# EasyEDA_Source.net
KiCad netlist of a schematic drawn in EasyEDA
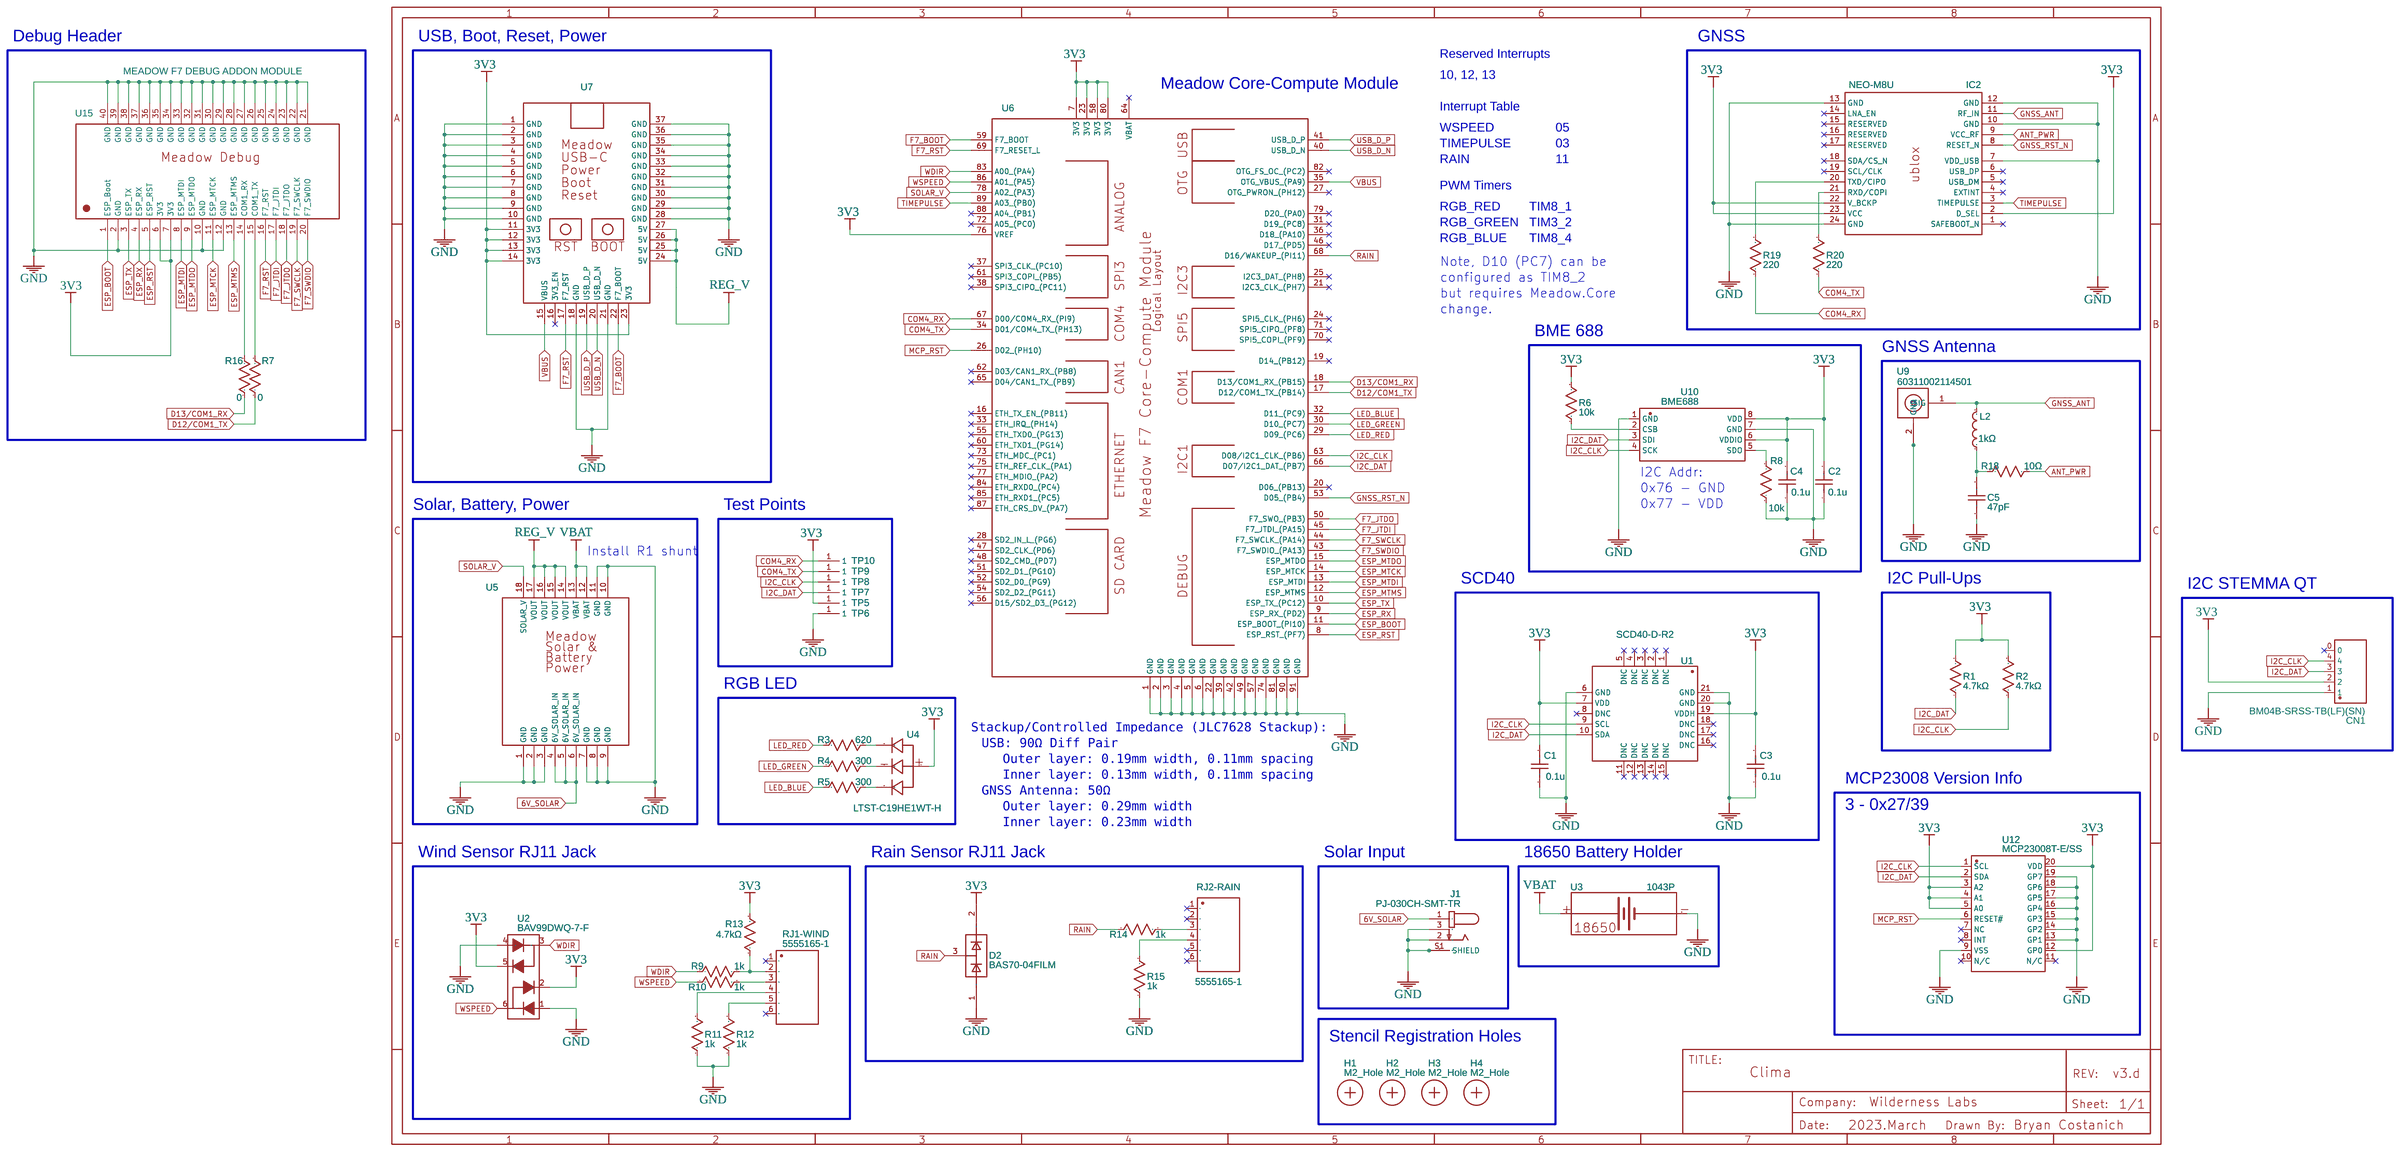
[diagram p0: schematic sheet]

(export (version "E")
  (design (tool "Eeschema 10.0.6"))
  (components
    (comp (ref "C1")
      (value "0.1u")
      (fields (field (name "BOM_Manufacturer Part") "CC0603KRX7R9BB103"))
      (libsource (lib "") (part "C_0402_US"))
    )
    (comp (ref "C2")
      (value "0.1u")
      (fields (field (name "BOM_Manufacturer Part") "CC0603KRX7R9BB103"))
      (libsource (lib "") (part "C_0402_US"))
    )
    (comp (ref "C3")
      (value "0.1u")
      (fields (field (name "BOM_Manufacturer Part") "CC0603KRX7R9BB103"))
      (libsource (lib "") (part "C_0402_US"))
    )
    (comp (ref "C4")
      (value "0.1u")
      (fields (field (name "BOM_Manufacturer Part") "CC0603KRX7R9BB103"))
      (libsource (lib "") (part "C_0402_US"))
    )
    (comp (ref "C5")
      (value "47pF")
      (fields (field (name "BOM_Manufacturer Part") "CC0603JRNPO9BN470"))
      (libsource (lib "") (part "C_0402_US"))
    )
    (comp (ref "CN1")
      (value "BM04B-SRSS-TB(LF)(SN)")
      (fields (field (name "BOM_Supplier Part") "C160390"))
      (libsource (lib "") (part "BM04B-SRSS-TB(LF)(SN)"))
    )
    (comp (ref "D2")
      (value "BAS70-04FILM")
      (fields (field (name "BOM_Supplier Part") "C283251"))
      (libsource (lib "") (part "BAS70-04FILM"))
    )
    (comp (ref "H1") (value "M2_Hole") (libsource (lib "") (part "Stencil_Registration_Hole")))
    (comp (ref "H2") (value "M2_Hole") (libsource (lib "") (part "Stencil_Registration_Hole")))
    (comp (ref "H3") (value "M2_Hole") (libsource (lib "") (part "Stencil_Registration_Hole")))
    (comp (ref "H4") (value "M2_Hole") (libsource (lib "") (part "Stencil_Registration_Hole")))
    (comp (ref "IC2") (value "NEO-M8U") (libsource (lib "") (part "UBLOX_NEO")))
    (comp (ref "J1") (value "PJ-030CH-SMT-TR") (libsource (lib "") (part "PJ-030CH-SMT-TR")))
    (comp (ref "L2")
      (value "1kΩ")
      (fields
        (field (name "BOM_Manufacturer Part") "BLM15HD102SN1D")
        (field (name "BOM_Supplier Part") "C21516")
      )
      (libsource (lib "") (part "BLM15HD102SN1D"))
    )
    (comp (ref "R1")
      (value "4.7kΩ")
      (fields (field (name "BOM_Manufacturer Part") "RC0603FR-074K7L"))
      (libsource (lib "") (part "Res_0603(1/10W)_US"))
    )
    (comp (ref "R2")
      (value "4.7kΩ")
      (fields (field (name "BOM_Manufacturer Part") "RC0603FR-074K7L"))
      (libsource (lib "") (part "Res_0603(1/10W)_US"))
    )
    (comp (ref "R3")
      (value "620")
      (fields (field (name "BOM_Manufacturer Part") "RC0603FR-07620RL"))
      (libsource (lib "") (part "R_0603_US_1"))
    )
    (comp (ref "R4")
      (value "300")
      (fields (field (name "BOM_Manufacturer Part") "RC0603FR-07300RL"))
      (libsource (lib "") (part "R_0603_US_1"))
    )
    (comp (ref "R5")
      (value "300")
      (fields (field (name "BOM_Manufacturer Part") "RC0603FR-07300RL"))
      (libsource (lib "") (part "R_0603_US_1"))
    )
    (comp (ref "R6")
      (value "10k")
      (fields (field (name "BOM_Manufacturer Part") "RC0603FR-0710KL"))
      (libsource (lib "") (part "R_0402_US"))
    )
    (comp (ref "R7")
      (value "0")
      (fields (field (name "BOM_Manufacturer Part") "RC0603JR-070RL"))
      (libsource (lib "") (part "R_0603_US"))
    )
    (comp (ref "R8")
      (value "10k")
      (fields (field (name "BOM_Manufacturer Part") "RC0603FR-0710KL"))
      (libsource (lib "") (part "R_0402_US"))
    )
    (comp (ref "R9")
      (value "1k")
      (fields (field (name "BOM_Manufacturer Part") "RC0603FR-071KL"))
      (libsource (lib "") (part "R_0402_US_1"))
    )
    (comp (ref "R10")
      (value "1k")
      (fields (field (name "BOM_Manufacturer Part") "RC0603FR-071KL"))
      (libsource (lib "") (part "R_0402_US_1"))
    )
    (comp (ref "R11")
      (value "1k")
      (fields (field (name "BOM_Manufacturer Part") "RC0603FR-071KL"))
      (libsource (lib "") (part "R_0402_US"))
    )
    (comp (ref "R12")
      (value "1k")
      (fields (field (name "BOM_Manufacturer Part") "RC0603FR-071KL"))
      (libsource (lib "") (part "R_0402_US"))
    )
    (comp (ref "R13")
      (value "4.7kΩ")
      (fields (field (name "BOM_Manufacturer Part") "RC0603FR-074K7L"))
      (libsource (lib "") (part "Res_0603(1/10W)_US"))
    )
    (comp (ref "R14")
      (value "1k")
      (fields (field (name "BOM_Manufacturer Part") "RC0603FR-071KL"))
      (libsource (lib "") (part "R_0402_US_1"))
    )
    (comp (ref "R15")
      (value "1k")
      (fields (field (name "BOM_Manufacturer Part") "RC0603FR-071KL"))
      (libsource (lib "") (part "R_0402_US"))
    )
    (comp (ref "R16")
      (value "0")
      (fields (field (name "BOM_Manufacturer Part") "RC0603JR-070RL"))
      (libsource (lib "") (part "R_0603_US"))
    )
    (comp (ref "R18")
      (value "10Ω")
      (fields (field (name "BOM_Manufacturer Part") "RC0603FR-0710RL"))
      (libsource (lib "") (part "R_0402_US_1"))
    )
    (comp (ref "R19")
      (value "220")
      (fields (field (name "BOM_Manufacturer Part") "RC0603FR-07220RL"))
      (libsource (lib "") (part "R_0603_US"))
    )
    (comp (ref "R20")
      (value "220")
      (fields (field (name "BOM_Manufacturer Part") "RC0603FR-07220RL"))
      (libsource (lib "") (part "R_0603_US"))
    )
    (comp (ref "RJ1-WIND")
      (value "5555165-1")
      (fields (field (name "BOM_Supplier Part") "C305981"))
      (libsource (lib "") (part "5555165-1_1"))
    )
    (comp (ref "RJ2-RAIN")
      (value "5555165-1")
      (fields (field (name "BOM_Supplier Part") "C305981"))
      (libsource (lib "") (part "5555165-1"))
    )
    (comp (ref "TP5") (value "TESTPAD_PTH") (libsource (lib "") (part "TESTPAD_PTH")))
    (comp (ref "TP6") (value "TESTPAD_PTH") (libsource (lib "") (part "TESTPAD_PTH")))
    (comp (ref "TP7") (value "TESTPAD_PTH") (libsource (lib "") (part "TESTPAD_PTH")))
    (comp (ref "TP8") (value "TESTPAD_PTH") (libsource (lib "") (part "TESTPAD_PTH")))
    (comp (ref "TP9") (value "TESTPAD_PTH") (libsource (lib "") (part "TESTPAD_PTH")))
    (comp (ref "TP10") (value "TESTPAD_PTH") (libsource (lib "") (part "TESTPAD_PTH")))
    (comp (ref "U1")
      (value "SCD40-D-R2")
      (fields (field (name "BOM_Supplier Part") "C9900009940"))
      (libsource (lib "") (part "SCD40-D-R2"))
    )
    (comp (ref "U2")
      (value "BAV99DWQ-7-F")
      (fields (field (name "BOM_Supplier Part") "BAV99DWQ-7-FDITR-ND"))
      (libsource (lib "") (part "BAV99DWQ-7-F"))
    )
    (comp (ref "U3") (value "1043P") (libsource (lib "") (part "1043P")))
    (comp (ref "U4")
      (value "LTST-C19HE1WT-H")
      (fields (field (name "BOM_Supplier Part") "C427425"))
      (libsource (lib "") (part "LTST-C19HE1WT-H"))
    )
    (comp (ref "U5")
      (value "Meadow Core-Compute Addon Module - Solar Battery Power")
      (libsource (lib "") (part "Meadow Core-Compute Addon Module - Solar Battery Power"))
    )
    (comp (ref "U6")
      (value "Meadow F7v2 Core-Compute Module - Logical")
      (libsource (lib "") (part "Meadow F7v2 Core-Compute Module - Logical"))
    )
    (comp (ref "U7")
      (value "Meadow Core-Compute USB-C, Power, Boot, and Reset Addon Module")
      (libsource (lib "") (part "Meadow Core-Compute USB-C, Power, Boot, and Reset Addon Module"))
    )
    (comp (ref "U8")
      (value "WILDERNESS_LABS_LOGO_HORIZONTAL")
      (libsource (lib "") (part "WILDERNESS_LABS_LOGO_HORIZONTAL"))
    )
    (comp (ref "U9") (value "60311002114501") (libsource (lib "") (part "60311002114501")))
    (comp (ref "U10") (value "BME688") (libsource (lib "") (part "BME680")))
    (comp (ref "U12")
      (value "MCP23008T-E/SS")
      (fields (field (name "BOM_Supplier Part") "C629435"))
      (libsource (lib "") (part "MCP23008T-E/SS"))
    )
    (comp (ref "U15")
      (value "MEADOW F7 DEBUG ADDON MODULE")
      (libsource (lib "") (part "MEADOW F7 DEBUG ADDON MODULE"))
    )
  )
  (nets
    (net (code "1") (name "3V3") (class "Default")
      (node (ref "C1") (pin "2") (pinfunction "2_2") (pintype "unspecified"))
      (node (ref "C2") (pin "2") (pinfunction "2_2") (pintype "unspecified"))
      (node (ref "C3") (pin "2") (pinfunction "2_2") (pintype "unspecified"))
      (node (ref "C4") (pin "2") (pinfunction "2_2") (pintype "unspecified"))
      (node (ref "CN1") (pin "2") (pinfunction "2_2") (pintype "unspecified"))
      (node (ref "D2") (pin "2") (pinfunction "C_2") (pintype "unspecified"))
      (node (ref "IC2") (pin "2") (pinfunction "D_SEL_2") (pintype "unspecified"))
      (node (ref "IC2") (pin "22") (pinfunction "V_BCKP_22") (pintype "unspecified"))
      (node (ref "IC2") (pin "23") (pinfunction "VCC_23") (pintype "unspecified"))
      (node (ref "R1") (pin "2") (pinfunction "2_2") (pintype "unspecified"))
      (node (ref "R13") (pin "2") (pinfunction "2_2") (pintype "unspecified"))
      (node (ref "R2") (pin "2") (pinfunction "2_2") (pintype "unspecified"))
      (node (ref "R6") (pin "2") (pinfunction "2_2") (pintype "unspecified"))
      (node (ref "TP5") (pin "1") (pinfunction "1_1") (pintype "unspecified"))
      (node (ref "U1") (pin "19") (pinfunction "VDDH_19") (pintype "unspecified"))
      (node (ref "U1") (pin "7") (pinfunction "VDD_7") (pintype "unspecified"))
      (node (ref "U10") (pin "6") (pinfunction "VDDIO_6") (pintype "unspecified"))
      (node (ref "U10") (pin "8") (pinfunction "VDD_8") (pintype "unspecified"))
      (node (ref "U12") (pin "12") (pinfunction "GP0_12") (pintype "unspecified"))
      (node (ref "U12") (pin "20") (pinfunction "VDD_20") (pintype "unspecified"))
      (node (ref "U12") (pin "3") (pinfunction "A2_3") (pintype "unspecified"))
      (node (ref "U12") (pin "4") (pinfunction "A1_4") (pintype "unspecified"))
      (node (ref "U12") (pin "5") (pinfunction "A0_5") (pintype "unspecified"))
      (node (ref "U15") (pin "6") (pinfunction "3V3_6") (pintype "unspecified"))
      (node (ref "U15") (pin "7") (pinfunction "3V3_7") (pintype "unspecified"))
      (node (ref "U2") (pin "2") (pinfunction "C1_2") (pintype "unspecified"))
      (node (ref "U2") (pin "5") (pinfunction "C2_5") (pintype "unspecified"))
      (node (ref "U4") (pin "4") (pinfunction "A_4") (pintype "unspecified"))
      (node (ref "U6") (pin "23") (pinfunction "3V3_23") (pintype "unspecified"))
      (node (ref "U6") (pin "58") (pinfunction "3V3_58") (pintype "passive"))
      (node (ref "U6") (pin "7") (pinfunction "3V3_7") (pintype "unspecified"))
      (node (ref "U6") (pin "76") (pinfunction "VREF_76") (pintype "input"))
      (node (ref "U6") (pin "80") (pinfunction "3V3_80") (pintype "unspecified"))
      (node (ref "U7") (pin "11") (pinfunction "3V3_11") (pintype "unspecified"))
      (node (ref "U7") (pin "12") (pinfunction "3V3_12") (pintype "unspecified"))
      (node (ref "U7") (pin "13") (pinfunction "3V3_13") (pintype "unspecified"))
      (node (ref "U7") (pin "14") (pinfunction "3V3_14") (pintype "unspecified"))
      (node (ref "U7") (pin "23") (pinfunction "3V3_23") (pintype "passive"))
    )
    (net (code "2") (name "6V_SOLAR") (class "Default")
      (node (ref "J1") (pin "1") (pinfunction "1_1") (pintype "bidirectional"))
      (node (ref "U5") (pin "4") (pinfunction "6V_SOLAR_IN_4") (pintype "unspecified"))
      (node (ref "U5") (pin "5") (pinfunction "6V_SOLAR_IN_5") (pintype "unspecified"))
      (node (ref "U5") (pin "6") (pinfunction "6V_SOLAR_IN_6") (pintype "unspecified"))
    )
    (net (code "3") (name "ANT_PWR") (class "Default")
      (node (ref "IC2") (pin "9") (pinfunction "VCC_RF_9") (pintype "unspecified"))
      (node (ref "R18") (pin "2") (pinfunction "2_2") (pintype "unspecified"))
    )
    (net (code "4") (name "COM4_RX") (class "Default")
      (node (ref "R19") (pin "1") (pinfunction "1_1") (pintype "unspecified"))
      (node (ref "TP10") (pin "1") (pinfunction "1_1") (pintype "unspecified"))
      (node (ref "U6") (pin "67") (pinfunction "D00/COM4_RX_(PI9)_67") (pintype "unspecified"))
    )
    (net (code "5") (name "COM4_TX") (class "Default")
      (node (ref "R20") (pin "1") (pinfunction "1_1") (pintype "unspecified"))
      (node (ref "TP9") (pin "1") (pinfunction "1_1") (pintype "unspecified"))
      (node (ref "U6") (pin "34") (pinfunction "D01/COM4_TX_(PH13)_34") (pintype "unspecified"))
    )
    (net (code "6") (name "D12{slash}COM1_TX") (class "Default")
      (node (ref "R7") (pin "1") (pinfunction "1_1") (pintype "unspecified"))
      (node (ref "U6") (pin "17") (pinfunction "D12/COM1_TX_(PB14)_17") (pintype "unspecified"))
    )
    (net (code "7") (name "D13{slash}COM1_RX") (class "Default")
      (node (ref "R16") (pin "1") (pinfunction "1_1") (pintype "unspecified"))
      (node (ref "U6") (pin "18") (pinfunction "D13/COM1_RX_(PB15)_18") (pintype "unspecified"))
    )
    (net (code "8") (name "ESP_BOOT") (class "Default")
      (node (ref "U15") (pin "1") (pinfunction "ESP_Boot_1") (pintype "unspecified"))
      (node (ref "U6") (pin "11") (pinfunction "ESP_BOOT_(PI10)_11") (pintype "unspecified"))
    )
    (net (code "9") (name "ESP_MTCK") (class "Default")
      (node (ref "U15") (pin "11") (pinfunction "ESP_MTCK_11") (pintype "unspecified"))
      (node (ref "U6") (pin "14") (pinfunction "ESP_MTCK_14") (pintype "unspecified"))
    )
    (net (code "10") (name "ESP_MTDI") (class "Default")
      (node (ref "U15") (pin "8") (pinfunction "ESP_MTDI_8") (pintype "unspecified"))
      (node (ref "U6") (pin "13") (pinfunction "ESP_MTDI_13") (pintype "unspecified"))
    )
    (net (code "11") (name "ESP_MTDO") (class "Default")
      (node (ref "U15") (pin "9") (pinfunction "ESP_MTDO_9") (pintype "unspecified"))
      (node (ref "U6") (pin "15") (pinfunction "ESP_MTDO_15") (pintype "unspecified"))
    )
    (net (code "12") (name "ESP_MTMS") (class "Default")
      (node (ref "U15") (pin "13") (pinfunction "ESP_MTMS_13") (pintype "unspecified"))
      (node (ref "U6") (pin "12") (pinfunction "ESP_MTMS_12") (pintype "unspecified"))
    )
    (net (code "13") (name "ESP_RST") (class "Default")
      (node (ref "U15") (pin "5") (pinfunction "ESP_RST_5") (pintype "unspecified"))
      (node (ref "U6") (pin "8") (pinfunction "ESP_RST_(PF7)_8") (pintype "unspecified"))
    )
    (net (code "14") (name "ESP_RX") (class "Default")
      (node (ref "U15") (pin "4") (pinfunction "ESP_RX_4") (pintype "unspecified"))
      (node (ref "U6") (pin "9") (pinfunction "ESP_RX_(PD2)_9") (pintype "unspecified"))
    )
    (net (code "15") (name "ESP_TX") (class "Default")
      (node (ref "U15") (pin "3") (pinfunction "ESP_TX_3") (pintype "unspecified"))
      (node (ref "U6") (pin "10") (pinfunction "ESP_TX_(PC12)_10") (pintype "unspecified"))
    )
    (net (code "16") (name "F7_BOOT") (class "Default")
      (node (ref "U6") (pin "59") (pinfunction "F7_BOOT_59") (pintype "unspecified"))
      (node (ref "U7") (pin "22") (pinfunction "F7_BOOT_22") (pintype "unspecified"))
    )
    (net (code "17") (name "F7_JTDI") (class "Default")
      (node (ref "U15") (pin "17") (pinfunction "F7_JTDI_17") (pintype "unspecified"))
      (node (ref "U6") (pin "45") (pinfunction "F7_JTDI_(PA15)_45") (pintype "unspecified"))
    )
    (net (code "18") (name "F7_JTDO") (class "Default")
      (node (ref "U15") (pin "18") (pinfunction "F7_JTDO_18") (pintype "unspecified"))
      (node (ref "U6") (pin "50") (pinfunction "F7_SWO_(PB3)_50") (pintype "unspecified"))
    )
    (net (code "19") (name "F7_RST") (class "Default")
      (node (ref "U15") (pin "16") (pinfunction "F7_RST_16") (pintype "unspecified"))
      (node (ref "U6") (pin "69") (pinfunction "F7_RESET_L_69") (pintype "unspecified"))
      (node (ref "U7") (pin "17") (pinfunction "F7_RST_17") (pintype "unspecified"))
    )
    (net (code "20") (name "F7_SWCLK") (class "Default")
      (node (ref "U15") (pin "19") (pinfunction "F7_SWCLK_19") (pintype "unspecified"))
      (node (ref "U6") (pin "44") (pinfunction "F7_SWCLK_(PA14)_44") (pintype "unspecified"))
    )
    (net (code "21") (name "F7_SWDIO") (class "Default")
      (node (ref "U15") (pin "20") (pinfunction "F7_SWDIO_20") (pintype "unspecified"))
      (node (ref "U6") (pin "43") (pinfunction "F7_SWDIO_(PA13)_43") (pintype "unspecified"))
    )
    (net (code "22") (name "GND") (class "Default")
      (node (ref "C1") (pin "1") (pinfunction "1_1") (pintype "unspecified"))
      (node (ref "C2") (pin "1") (pinfunction "1_1") (pintype "unspecified"))
      (node (ref "C3") (pin "1") (pinfunction "1_1") (pintype "unspecified"))
      (node (ref "C4") (pin "1") (pinfunction "1_1") (pintype "unspecified"))
      (node (ref "C5") (pin "1") (pinfunction "1_1") (pintype "unspecified"))
      (node (ref "CN1") (pin "1") (pinfunction "1_1") (pintype "unspecified"))
      (node (ref "D2") (pin "1") (pinfunction "A_1") (pintype "unspecified"))
      (node (ref "IC2") (pin "10") (pinfunction "GND_10") (pintype "unspecified"))
      (node (ref "IC2") (pin "12") (pinfunction "GND_12") (pintype "unspecified"))
      (node (ref "IC2") (pin "13") (pinfunction "GND_13") (pintype "unspecified"))
      (node (ref "IC2") (pin "24") (pinfunction "GND_24") (pintype "unspecified"))
      (node (ref "IC2") (pin "7") (pinfunction "VDD_USB_7") (pintype "unspecified"))
      (node (ref "J1") (pin "2") (pinfunction "2_2") (pintype "bidirectional"))
      (node (ref "J1") (pin "3") (pinfunction "3_3") (pintype "bidirectional"))
      (node (ref "J1") (pin "S1") (pinfunction "SHIELD_S1") (pintype "bidirectional"))
      (node (ref "J1") (pin "S2") (pinfunction "SHIELD_S2") (pintype "bidirectional"))
      (node (ref "R11") (pin "1") (pinfunction "1_1") (pintype "unspecified"))
      (node (ref "R12") (pin "1") (pinfunction "1_1") (pintype "unspecified"))
      (node (ref "R15") (pin "1") (pinfunction "1_1") (pintype "unspecified"))
      (node (ref "R8") (pin "1") (pinfunction "1_1") (pintype "unspecified"))
      (node (ref "TP6") (pin "1") (pinfunction "1_1") (pintype "unspecified"))
      (node (ref "U1") (pin "20") (pinfunction "GND_20") (pintype "unspecified"))
      (node (ref "U1") (pin "21") (pinfunction "GND_21") (pintype "unspecified"))
      (node (ref "U1") (pin "6") (pinfunction "GND_6") (pintype "unspecified"))
      (node (ref "U10") (pin "1") (pinfunction "GND_1") (pintype "unspecified"))
      (node (ref "U10") (pin "7") (pinfunction "GND_7") (pintype "unspecified"))
      (node (ref "U12") (pin "13") (pinfunction "GP1_13") (pintype "unspecified"))
      (node (ref "U12") (pin "14") (pinfunction "GP2_14") (pintype "unspecified"))
      (node (ref "U12") (pin "15") (pinfunction "GP3_15") (pintype "unspecified"))
      (node (ref "U12") (pin "16") (pinfunction "GP4_16") (pintype "unspecified"))
      (node (ref "U12") (pin "17") (pinfunction "GP5_17") (pintype "unspecified"))
      (node (ref "U12") (pin "18") (pinfunction "GP6_18") (pintype "unspecified"))
      (node (ref "U12") (pin "19") (pinfunction "GP7_19") (pintype "unspecified"))
      (node (ref "U12") (pin "9") (pinfunction "VSS_9") (pintype "unspecified"))
      (node (ref "U15") (pin "10") (pinfunction "GND_10") (pintype "unspecified"))
      (node (ref "U15") (pin "12") (pinfunction "GND_12") (pintype "unspecified"))
      (node (ref "U15") (pin "2") (pinfunction "GND_2") (pintype "unspecified"))
      (node (ref "U15") (pin "21") (pinfunction "GND_21") (pintype "unspecified"))
      (node (ref "U15") (pin "22") (pinfunction "GND_22") (pintype "unspecified"))
      (node (ref "U15") (pin "23") (pinfunction "GND_23") (pintype "unspecified"))
      (node (ref "U15") (pin "24") (pinfunction "GND_24") (pintype "unspecified"))
      (node (ref "U15") (pin "25") (pinfunction "GND_25") (pintype "unspecified"))
      (node (ref "U15") (pin "26") (pinfunction "GND_26") (pintype "unspecified"))
      (node (ref "U15") (pin "27") (pinfunction "GND_27") (pintype "unspecified"))
      (node (ref "U15") (pin "28") (pinfunction "GND_28") (pintype "unspecified"))
      (node (ref "U15") (pin "29") (pinfunction "GND_29") (pintype "unspecified"))
      (node (ref "U15") (pin "30") (pinfunction "GND_30") (pintype "unspecified"))
      (node (ref "U15") (pin "31") (pinfunction "GND_31") (pintype "unspecified"))
      (node (ref "U15") (pin "32") (pinfunction "GND_32") (pintype "unspecified"))
      (node (ref "U15") (pin "33") (pinfunction "GND_33") (pintype "unspecified"))
      (node (ref "U15") (pin "34") (pinfunction "GND_34") (pintype "unspecified"))
      (node (ref "U15") (pin "35") (pinfunction "GND_35") (pintype "unspecified"))
      (node (ref "U15") (pin "36") (pinfunction "GND_36") (pintype "unspecified"))
      (node (ref "U15") (pin "37") (pinfunction "GND_37") (pintype "unspecified"))
      (node (ref "U15") (pin "38") (pinfunction "GND_38") (pintype "unspecified"))
      (node (ref "U15") (pin "39") (pinfunction "GND_39") (pintype "unspecified"))
      (node (ref "U15") (pin "40") (pinfunction "GND_40") (pintype "unspecified"))
      (node (ref "U2") (pin "1") (pinfunction "A1_1") (pintype "unspecified"))
      (node (ref "U2") (pin "4") (pinfunction "A2_4") (pintype "unspecified"))
      (node (ref "U3") (pin "2") (pinfunction "-_2") (pintype "passive"))
      (node (ref "U5") (pin "1") (pinfunction "GND_1") (pintype "unspecified"))
      (node (ref "U5") (pin "10") (pinfunction "GND_10") (pintype "unspecified"))
      (node (ref "U5") (pin "11") (pinfunction "GND_11") (pintype "unspecified"))
      (node (ref "U5") (pin "2") (pinfunction "GND_2") (pintype "unspecified"))
      (node (ref "U5") (pin "3") (pinfunction "GND_3") (pintype "unspecified"))
      (node (ref "U5") (pin "7") (pinfunction "GND_7") (pintype "unspecified"))
      (node (ref "U5") (pin "8") (pinfunction "GND_8") (pintype "unspecified"))
      (node (ref "U5") (pin "9") (pinfunction "GND_9") (pintype "unspecified"))
      (node (ref "U6") (pin "1") (pinfunction "GND_1") (pintype "passive"))
      (node (ref "U6") (pin "2") (pinfunction "GND_2") (pintype "passive"))
      (node (ref "U6") (pin "22") (pinfunction "GND_22") (pintype "passive"))
      (node (ref "U6") (pin "3") (pinfunction "GND_3") (pintype "passive"))
      (node (ref "U6") (pin "39") (pinfunction "GND_39") (pintype "passive"))
      (node (ref "U6") (pin "4") (pinfunction "GND_4") (pintype "passive"))
      (node (ref "U6") (pin "42") (pinfunction "GND_42") (pintype "passive"))
      (node (ref "U6") (pin "49") (pinfunction "GND_49") (pintype "passive"))
      (node (ref "U6") (pin "5") (pinfunction "GND_5") (pintype "passive"))
      (node (ref "U6") (pin "57") (pinfunction "GND_57") (pintype "passive"))
      (node (ref "U6") (pin "6") (pinfunction "GND_6") (pintype "passive"))
      (node (ref "U6") (pin "74") (pinfunction "GND_74") (pintype "passive"))
      (node (ref "U6") (pin "81") (pinfunction "GND_81") (pintype "passive"))
      (node (ref "U6") (pin "90") (pinfunction "GND_90") (pintype "passive"))
      (node (ref "U6") (pin "91") (pinfunction "GND_91") (pintype "passive"))
      (node (ref "U7") (pin "1") (pinfunction "GND_1") (pintype "unspecified"))
      (node (ref "U7") (pin "10") (pinfunction "GND_10") (pintype "unspecified"))
      (node (ref "U7") (pin "18") (pinfunction "GND_18") (pintype "unspecified"))
      (node (ref "U7") (pin "2") (pinfunction "GND_2") (pintype "unspecified"))
      (node (ref "U7") (pin "21") (pinfunction "GND_21") (pintype "unspecified"))
      (node (ref "U7") (pin "28") (pinfunction "GND_28") (pintype "unspecified"))
      (node (ref "U7") (pin "29") (pinfunction "GND_29") (pintype "unspecified"))
      (node (ref "U7") (pin "3") (pinfunction "GND_3") (pintype "unspecified"))
      (node (ref "U7") (pin "30") (pinfunction "GND_30") (pintype "unspecified"))
      (node (ref "U7") (pin "31") (pinfunction "GND_31") (pintype "unspecified"))
      (node (ref "U7") (pin "32") (pinfunction "GND_32") (pintype "unspecified"))
      (node (ref "U7") (pin "33") (pinfunction "GND_33") (pintype "unspecified"))
      (node (ref "U7") (pin "34") (pinfunction "GND_34") (pintype "unspecified"))
      (node (ref "U7") (pin "35") (pinfunction "GND_35") (pintype "unspecified"))
      (node (ref "U7") (pin "36") (pinfunction "GND_36") (pintype "unspecified"))
      (node (ref "U7") (pin "37") (pinfunction "GND_37") (pintype "unspecified"))
      (node (ref "U7") (pin "4") (pinfunction "GND_4") (pintype "unspecified"))
      (node (ref "U7") (pin "5") (pinfunction "GND_5") (pintype "unspecified"))
      (node (ref "U7") (pin "6") (pinfunction "GND_6") (pintype "unspecified"))
      (node (ref "U7") (pin "7") (pinfunction "GND_7") (pintype "unspecified"))
      (node (ref "U7") (pin "8") (pinfunction "GND_8") (pintype "unspecified"))
      (node (ref "U7") (pin "9") (pinfunction "GND_9") (pintype "unspecified"))
      (node (ref "U9") (pin "2") (pinfunction "GND_2") (pintype "unspecified"))
    )
    (net (code "23") (name "GNSS_ANT") (class "Default")
      (node (ref "IC2") (pin "11") (pinfunction "RF_IN_11") (pintype "unspecified"))
      (node (ref "L2") (pin "2") (pinfunction "2_2") (pintype "unspecified"))
      (node (ref "U9") (pin "1") (pinfunction "SIG_1") (pintype "unspecified"))
    )
    (net (code "24") (name "GNSS_RST_N") (class "Default")
      (node (ref "IC2") (pin "8") (pinfunction "RESET_N_8") (pintype "unspecified"))
      (node (ref "U6") (pin "53") (pinfunction "D05_(PB4)_53") (pintype "unspecified"))
    )
    (net (code "25") (name "I2C_CLK") (class "Default")
      (node (ref "CN1") (pin "4") (pinfunction "4_4") (pintype "unspecified"))
      (node (ref "R2") (pin "1") (pinfunction "1_1") (pintype "unspecified"))
      (node (ref "TP8") (pin "1") (pinfunction "1_1") (pintype "unspecified"))
      (node (ref "U1") (pin "9") (pinfunction "SCL_9") (pintype "unspecified"))
      (node (ref "U10") (pin "4") (pinfunction "SCK_4") (pintype "unspecified"))
      (node (ref "U12") (pin "1") (pinfunction "SCL_1") (pintype "unspecified"))
      (node (ref "U6") (pin "63") (pinfunction "D08/I2C1_CLK_(PB6)_63") (pintype "unspecified"))
    )
    (net (code "26") (name "I2C_DAT") (class "Default")
      (node (ref "CN1") (pin "3") (pinfunction "3_3") (pintype "unspecified"))
      (node (ref "R1") (pin "1") (pinfunction "1_1") (pintype "unspecified"))
      (node (ref "TP7") (pin "1") (pinfunction "1_1") (pintype "unspecified"))
      (node (ref "U1") (pin "10") (pinfunction "SDA_10") (pintype "unspecified"))
      (node (ref "U10") (pin "3") (pinfunction "SDI_3") (pintype "unspecified"))
      (node (ref "U12") (pin "2") (pinfunction "SDA_2") (pintype "unspecified"))
      (node (ref "U6") (pin "66") (pinfunction "D07/I2C1_DAT_(PB7)_66") (pintype "unspecified"))
    )
    (net (code "27") (name "LED_BLUE") (class "Default")
      (node (ref "R5") (pin "1") (pinfunction "1_1") (pintype "unspecified"))
      (node (ref "U6") (pin "32") (pinfunction "D11_(PC9)_32") (pintype "unspecified"))
    )
    (net (code "28") (name "LED_GREEN") (class "Default")
      (node (ref "R4") (pin "1") (pinfunction "1_1") (pintype "unspecified"))
      (node (ref "U6") (pin "30") (pinfunction "D10_(PC7)_30") (pintype "unspecified"))
    )
    (net (code "29") (name "LED_RED") (class "Default")
      (node (ref "R3") (pin "1") (pinfunction "1_1") (pintype "unspecified"))
      (node (ref "U6") (pin "29") (pinfunction "D09_(PC6)_29") (pintype "unspecified"))
    )
    (net (code "30") (name "MCP_RST") (class "Default")
      (node (ref "U12") (pin "6") (pinfunction "RESET#_6") (pintype "unspecified"))
      (node (ref "U6") (pin "26") (pinfunction "D02_(PH10)_26") (pintype "unspecified"))
    )
    (net (code "31") (name "Net-(C5-Pad2)") (class "Default")
      (node (ref "C5") (pin "2") (pinfunction "2_2") (pintype "unspecified"))
      (node (ref "L2") (pin "1") (pinfunction "1_1") (pintype "unspecified"))
      (node (ref "R18") (pin "1") (pinfunction "1_1") (pintype "unspecified"))
    )
    (net (code "32") (name "Net-(IC2-RXD{slash}COPI)") (class "Default")
      (node (ref "IC2") (pin "21") (pinfunction "RXD/COPI_21") (pintype "unspecified"))
      (node (ref "R20") (pin "2") (pinfunction "2_2") (pintype "unspecified"))
    )
    (net (code "33") (name "Net-(IC2-TXD{slash}CIPO)") (class "Default")
      (node (ref "IC2") (pin "20") (pinfunction "TXD/CIPO_20") (pintype "unspecified"))
      (node (ref "R19") (pin "2") (pinfunction "2_2") (pintype "unspecified"))
    )
    (net (code "34") (name "Net-(R10-Pad2)") (class "Default")
      (node (ref "R10") (pin "2") (pinfunction "2_2") (pintype "unspecified"))
      (node (ref "RJ1-WIND") (pin "3") (pinfunction "3_3") (pintype "unspecified"))
    )
    (net (code "35") (name "Net-(R11-Pad2)") (class "Default")
      (node (ref "R11") (pin "2") (pinfunction "2_2") (pintype "unspecified"))
      (node (ref "RJ1-WIND") (pin "4") (pinfunction "4_4") (pintype "unspecified"))
    )
    (net (code "36") (name "Net-(R12-Pad2)") (class "Default")
      (node (ref "R12") (pin "2") (pinfunction "2_2") (pintype "unspecified"))
      (node (ref "RJ1-WIND") (pin "5") (pinfunction "5_5") (pintype "unspecified"))
    )
    (net (code "37") (name "Net-(R13-Pad1)") (class "Default")
      (node (ref "R13") (pin "1") (pinfunction "1_1") (pintype "unspecified"))
      (node (ref "R9") (pin "2") (pinfunction "2_2") (pintype "unspecified"))
      (node (ref "RJ1-WIND") (pin "2") (pinfunction "2_2") (pintype "unspecified"))
    )
    (net (code "38") (name "Net-(R14-Pad2)") (class "Default")
      (node (ref "R14") (pin "2") (pinfunction "2_2") (pintype "unspecified"))
      (node (ref "RJ2-RAIN") (pin "3") (pinfunction "3_3") (pintype "unspecified"))
    )
    (net (code "39") (name "Net-(R15-Pad2)") (class "Default")
      (node (ref "R15") (pin "2") (pinfunction "2_2") (pintype "unspecified"))
      (node (ref "RJ2-RAIN") (pin "4") (pinfunction "4_4") (pintype "unspecified"))
    )
    (net (code "40") (name "Net-(U4-C1)") (class "Default")
      (node (ref "R3") (pin "2") (pinfunction "2_2") (pintype "unspecified"))
      (node (ref "U4") (pin "1") (pinfunction "C1_1") (pintype "unspecified"))
    )
    (net (code "41") (name "Net-(U4-C2)") (class "Default")
      (node (ref "R4") (pin "2") (pinfunction "2_2") (pintype "unspecified"))
      (node (ref "U4") (pin "2") (pinfunction "C2_2") (pintype "unspecified"))
    )
    (net (code "42") (name "Net-(U4-C3)") (class "Default")
      (node (ref "R5") (pin "2") (pinfunction "2_2") (pintype "unspecified"))
      (node (ref "U4") (pin "3") (pinfunction "C3_3") (pintype "unspecified"))
    )
    (net (code "43") (name "Net-(U10-CSB)") (class "Default")
      (node (ref "R6") (pin "1") (pinfunction "1_1") (pintype "unspecified"))
      (node (ref "U10") (pin "2") (pinfunction "CSB_2") (pintype "unspecified"))
    )
    (net (code "44") (name "Net-(U10-SDO)") (class "Default")
      (node (ref "R8") (pin "2") (pinfunction "2_2") (pintype "unspecified"))
      (node (ref "U10") (pin "5") (pinfunction "SDO_5") (pintype "unspecified"))
    )
    (net (code "45") (name "Net-(U15-COM1_RX)") (class "Default")
      (node (ref "R16") (pin "2") (pinfunction "2_2") (pintype "unspecified"))
      (node (ref "U15") (pin "14") (pinfunction "COM1_RX_14") (pintype "unspecified"))
    )
    (net (code "46") (name "Net-(U15-COM1_TX)") (class "Default")
      (node (ref "R7") (pin "2") (pinfunction "2_2") (pintype "unspecified"))
      (node (ref "U15") (pin "15") (pinfunction "COM1_TX_15") (pintype "unspecified"))
    )
    (net (code "47") (name "RAIN") (class "Default")
      (node (ref "D2") (pin "3") (pinfunction "A/C_3") (pintype "unspecified"))
      (node (ref "R14") (pin "1") (pinfunction "1_1") (pintype "unspecified"))
      (node (ref "U6") (pin "68") (pinfunction "D16/WAKEUP_(PI11)_68") (pintype "unspecified"))
    )
    (net (code "48") (name "REG_V") (class "Default")
      (node (ref "U5") (pin "14") (pinfunction "VOUT_14") (pintype "unspecified"))
      (node (ref "U5") (pin "15") (pinfunction "VOUT_15") (pintype "unspecified"))
      (node (ref "U5") (pin "16") (pinfunction "VOUT_16") (pintype "unspecified"))
      (node (ref "U5") (pin "17") (pinfunction "VOUT_17") (pintype "unspecified"))
      (node (ref "U7") (pin "24") (pinfunction "5V_24") (pintype "passive"))
      (node (ref "U7") (pin "25") (pinfunction "5V_25") (pintype "passive"))
      (node (ref "U7") (pin "26") (pinfunction "5V_26") (pintype "passive"))
      (node (ref "U7") (pin "27") (pinfunction "5V_27") (pintype "passive"))
    )
    (net (code "49") (name "SOLAR_V") (class "Default")
      (node (ref "U5") (pin "18") (pinfunction "SOLAR_V_18") (pintype "unspecified"))
      (node (ref "U6") (pin "78") (pinfunction "A02_(PA3)_78") (pintype "unspecified"))
    )
    (net (code "50") (name "TIMEPULSE") (class "Default")
      (node (ref "IC2") (pin "3") (pinfunction "TIMEPULSE_3") (pintype "unspecified"))
      (node (ref "U6") (pin "89") (pinfunction "A03_(PB0)_89") (pintype "unspecified"))
    )
    (net (code "51") (name "USB_D_N") (class "Default")
      (node (ref "U6") (pin "40") (pinfunction "USB_D_N_40") (pintype "unspecified"))
      (node (ref "U7") (pin "20") (pinfunction "USB_D_N_20") (pintype "unspecified"))
    )
    (net (code "52") (name "USB_D_P") (class "Default")
      (node (ref "U6") (pin "41") (pinfunction "USB_D_P_41") (pintype "unspecified"))
      (node (ref "U7") (pin "19") (pinfunction "USB_D_P_19") (pintype "unspecified"))
    )
    (net (code "53") (name "VBAT") (class "Default")
      (node (ref "U3") (pin "1") (pinfunction "+_1") (pintype "passive"))
      (node (ref "U5") (pin "12") (pinfunction "VBAT_12") (pintype "unspecified"))
      (node (ref "U5") (pin "13") (pinfunction "VBAT_13") (pintype "unspecified"))
    )
    (net (code "54") (name "VBUS") (class "Default")
      (node (ref "U6") (pin "35") (pinfunction "OTG_VBUS_(PA9)_35") (pintype "unspecified"))
      (node (ref "U7") (pin "15") (pinfunction "VBUS_15") (pintype "unspecified"))
    )
    (net (code "55") (name "WDIR") (class "Default")
      (node (ref "R9") (pin "1") (pinfunction "1_1") (pintype "unspecified"))
      (node (ref "U2") (pin "3") (pinfunction "AC2_3") (pintype "unspecified"))
      (node (ref "U6") (pin "83") (pinfunction "A00_(PA4)_83") (pintype "unspecified"))
    )
    (net (code "56") (name "WSPEED") (class "Default")
      (node (ref "R10") (pin "1") (pinfunction "1_1") (pintype "unspecified"))
      (node (ref "U2") (pin "6") (pinfunction "AC_6") (pintype "unspecified"))
      (node (ref "U6") (pin "86") (pinfunction "A01_(PA5)_86") (pintype "unspecified"))
    )
    (net (code "57") (name "unconnected-(CN1-Pad0)") (class "Default")
      (node (ref "CN1") (pin "0") (pinfunction "0_0") (pintype "unspecified+no_connect"))
    )
    (net (code "58") (name "unconnected-(IC2-EXTINT-Pad4)") (class "Default")
      (node (ref "IC2") (pin "4") (pinfunction "EXTINT_4") (pintype "unspecified+no_connect"))
    )
    (net (code "59") (name "unconnected-(IC2-LNA_EN-Pad14)") (class "Default")
      (node (ref "IC2") (pin "14") (pinfunction "LNA_EN_14") (pintype "unspecified+no_connect"))
    )
    (net (code "60") (name "unconnected-(IC2-RESERVED-Pad15)") (class "Default")
      (node (ref "IC2") (pin "15") (pinfunction "RESERVED_15") (pintype "unspecified+no_connect"))
    )
    (net (code "61") (name "unconnected-(IC2-RESERVED-Pad16)") (class "Default")
      (node (ref "IC2") (pin "16") (pinfunction "RESERVED_16") (pintype "unspecified+no_connect"))
    )
    (net (code "62") (name "unconnected-(IC2-RESERVED-Pad17)") (class "Default")
      (node (ref "IC2") (pin "17") (pinfunction "RESERVED_17") (pintype "unspecified+no_connect"))
    )
    (net (code "63") (name "unconnected-(IC2-SAFEBOOT_N-Pad1)") (class "Default")
      (node (ref "IC2") (pin "1") (pinfunction "SAFEBOOT_N_1") (pintype "unspecified+no_connect"))
    )
    (net (code "64") (name "unconnected-(IC2-SCL{slash}CLK-Pad19)") (class "Default")
      (node (ref "IC2") (pin "19") (pinfunction "SCL/CLK_19") (pintype "unspecified+no_connect"))
    )
    (net (code "65") (name "unconnected-(IC2-SDA{slash}CS_N-Pad18)") (class "Default")
      (node (ref "IC2") (pin "18") (pinfunction "SDA/CS_N_18") (pintype "unspecified+no_connect"))
    )
    (net (code "66") (name "unconnected-(IC2-USB_DM-Pad5)") (class "Default")
      (node (ref "IC2") (pin "5") (pinfunction "USB_DM_5") (pintype "unspecified+no_connect"))
    )
    (net (code "67") (name "unconnected-(IC2-USB_DP-Pad6)") (class "Default")
      (node (ref "IC2") (pin "6") (pinfunction "USB_DP_6") (pintype "unspecified+no_connect"))
    )
    (net (code "68") (name "unconnected-(RJ1-WIND-Pad1)") (class "Default")
      (node (ref "RJ1-WIND") (pin "1") (pinfunction "1_1") (pintype "unspecified+no_connect"))
    )
    (net (code "69") (name "unconnected-(RJ1-WIND-Pad6)") (class "Default")
      (node (ref "RJ1-WIND") (pin "6") (pinfunction "6_6") (pintype "unspecified+no_connect"))
    )
    (net (code "70") (name "unconnected-(RJ2-RAIN-Pad1)") (class "Default")
      (node (ref "RJ2-RAIN") (pin "1") (pinfunction "1_1") (pintype "unspecified+no_connect"))
    )
    (net (code "71") (name "unconnected-(RJ2-RAIN-Pad2)") (class "Default")
      (node (ref "RJ2-RAIN") (pin "2") (pinfunction "2_2") (pintype "unspecified+no_connect"))
    )
    (net (code "72") (name "unconnected-(RJ2-RAIN-Pad5)") (class "Default")
      (node (ref "RJ2-RAIN") (pin "5") (pinfunction "5_5") (pintype "unspecified+no_connect"))
    )
    (net (code "73") (name "unconnected-(RJ2-RAIN-Pad6)") (class "Default")
      (node (ref "RJ2-RAIN") (pin "6") (pinfunction "6_6") (pintype "unspecified+no_connect"))
    )
    (net (code "74") (name "unconnected-(U1-DNC-Pad1)") (class "Default")
      (node (ref "U1") (pin "1") (pinfunction "DNC_1") (pintype "unspecified+no_connect"))
    )
    (net (code "75") (name "unconnected-(U1-DNC-Pad2)") (class "Default")
      (node (ref "U1") (pin "2") (pinfunction "DNC_2") (pintype "unspecified+no_connect"))
    )
    (net (code "76") (name "unconnected-(U1-DNC-Pad3)") (class "Default")
      (node (ref "U1") (pin "3") (pinfunction "DNC_3") (pintype "unspecified+no_connect"))
    )
    (net (code "77") (name "unconnected-(U1-DNC-Pad4)") (class "Default")
      (node (ref "U1") (pin "4") (pinfunction "DNC_4") (pintype "unspecified+no_connect"))
    )
    (net (code "78") (name "unconnected-(U1-DNC-Pad5)") (class "Default")
      (node (ref "U1") (pin "5") (pinfunction "DNC_5") (pintype "unspecified+no_connect"))
    )
    (net (code "79") (name "unconnected-(U1-DNC-Pad8)") (class "Default")
      (node (ref "U1") (pin "8") (pinfunction "DNC_8") (pintype "unspecified+no_connect"))
    )
    (net (code "80") (name "unconnected-(U1-DNC-Pad11)") (class "Default")
      (node (ref "U1") (pin "11") (pinfunction "DNC_11") (pintype "unspecified+no_connect"))
    )
    (net (code "81") (name "unconnected-(U1-DNC-Pad12)") (class "Default")
      (node (ref "U1") (pin "12") (pinfunction "DNC_12") (pintype "unspecified+no_connect"))
    )
    (net (code "82") (name "unconnected-(U1-DNC-Pad13)") (class "Default")
      (node (ref "U1") (pin "13") (pinfunction "DNC_13") (pintype "unspecified+no_connect"))
    )
    (net (code "83") (name "unconnected-(U1-DNC-Pad14)") (class "Default")
      (node (ref "U1") (pin "14") (pinfunction "DNC_14") (pintype "unspecified+no_connect"))
    )
    (net (code "84") (name "unconnected-(U1-DNC-Pad15)") (class "Default")
      (node (ref "U1") (pin "15") (pinfunction "DNC_15") (pintype "unspecified+no_connect"))
    )
    (net (code "85") (name "unconnected-(U1-DNC-Pad16)") (class "Default")
      (node (ref "U1") (pin "16") (pinfunction "DNC_16") (pintype "unspecified+no_connect"))
    )
    (net (code "86") (name "unconnected-(U1-DNC-Pad17)") (class "Default")
      (node (ref "U1") (pin "17") (pinfunction "DNC_17") (pintype "unspecified+no_connect"))
    )
    (net (code "87") (name "unconnected-(U1-DNC-Pad18)") (class "Default")
      (node (ref "U1") (pin "18") (pinfunction "DNC_18") (pintype "unspecified+no_connect"))
    )
    (net (code "88") (name "unconnected-(U6-A04_(PB1)-Pad88)") (class "Default")
      (node (ref "U6") (pin "88") (pinfunction "A04_(PB1)_88") (pintype "unspecified+no_connect"))
    )
    (net (code "89") (name "unconnected-(U6-A05_(PC0)-Pad72)") (class "Default")
      (node (ref "U6") (pin "72") (pinfunction "A05_(PC0)_72") (pintype "unspecified+no_connect"))
    )
    (net (code "90") (name "unconnected-(U6-D03{slash}CAN1_RX_(PB8)-Pad62)") (class "Default")
      (node (ref "U6") (pin "62") (pinfunction "D03/CAN1_RX_(PB8)_62") (pintype "unspecified+no_connect"))
    )
    (net (code "91") (name "unconnected-(U6-D04{slash}CAN1_TX_(PB9)-Pad65)") (class "Default")
      (node (ref "U6") (pin "65") (pinfunction "D04/CAN1_TX_(PB9)_65") (pintype "unspecified+no_connect"))
    )
    (net (code "92") (name "unconnected-(U6-D06_(PB13)-Pad20)") (class "Default")
      (node (ref "U6") (pin "20") (pinfunction "D06_(PB13)_20") (pintype "unspecified+no_connect"))
    )
    (net (code "93") (name "unconnected-(U6-D14_(PB12)-Pad19)") (class "Default")
      (node (ref "U6") (pin "19") (pinfunction "D14_(PB12)_19") (pintype "unspecified+no_connect"))
    )
    (net (code "94") (name "unconnected-(U6-D15{slash}SD2_D3_(PG12)-Pad56)") (class "Default")
      (node (ref "U6") (pin "56") (pinfunction "D15/SD2_D3_(PG12)_56") (pintype "unspecified+no_connect"))
    )
    (net (code "95") (name "unconnected-(U6-D17_(PD5)-Pad46)") (class "Default")
      (node (ref "U6") (pin "46") (pinfunction "D17_(PD5)_46") (pintype "unspecified+no_connect"))
    )
    (net (code "96") (name "unconnected-(U6-D18_(PA10)-Pad36)") (class "Default")
      (node (ref "U6") (pin "36") (pinfunction "D18_(PA10)_36") (pintype "unspecified+no_connect"))
    )
    (net (code "97") (name "unconnected-(U6-D19_(PC8)-Pad31)") (class "Default")
      (node (ref "U6") (pin "31") (pinfunction "D19_(PC8)_31") (pintype "unspecified+no_connect"))
    )
    (net (code "98") (name "unconnected-(U6-D20_(PA0)-Pad79)") (class "Default")
      (node (ref "U6") (pin "79") (pinfunction "D20_(PA0)_79") (pintype "unspecified+no_connect"))
    )
    (net (code "99") (name "unconnected-(U6-ETH_CRS_DV_(PA7)-Pad87)") (class "Default")
      (node (ref "U6") (pin "87") (pinfunction "ETH_CRS_DV_(PA7)_87") (pintype "unspecified+no_connect"))
    )
    (net (code "100") (name "unconnected-(U6-ETH_IRQ_(PH14)-Pad33)") (class "Default")
      (node (ref "U6") (pin "33") (pinfunction "ETH_IRQ_(PH14)_33") (pintype "unspecified+no_connect"))
    )
    (net (code "101") (name "unconnected-(U6-ETH_MDC_(PC1)-Pad73)") (class "Default")
      (node (ref "U6") (pin "73") (pinfunction "ETH_MDC_(PC1)_73") (pintype "unspecified+no_connect"))
    )
    (net (code "102") (name "unconnected-(U6-ETH_MDIO_(PA2)-Pad77)") (class "Default")
      (node (ref "U6") (pin "77") (pinfunction "ETH_MDIO_(PA2)_77") (pintype "unspecified+no_connect"))
    )
    (net (code "103") (name "unconnected-(U6-ETH_REF_CLK_(PA1)-Pad75)") (class "Default")
      (node (ref "U6") (pin "75") (pinfunction "ETH_REF_CLK_(PA1)_75") (pintype "unspecified+no_connect"))
    )
    (net (code "104") (name "unconnected-(U6-ETH_RXD0_(PC4)-Pad84)") (class "Default")
      (node (ref "U6") (pin "84") (pinfunction "ETH_RXD0_(PC4)_84") (pintype "unspecified+no_connect"))
    )
    (net (code "105") (name "unconnected-(U6-ETH_RXD1_(PC5)-Pad85)") (class "Default")
      (node (ref "U6") (pin "85") (pinfunction "ETH_RXD1_(PC5)_85") (pintype "unspecified+no_connect"))
    )
    (net (code "106") (name "unconnected-(U6-ETH_TXD0_(PG13)-Pad55)") (class "Default")
      (node (ref "U6") (pin "55") (pinfunction "ETH_TXD0_(PG13)_55") (pintype "unspecified+no_connect"))
    )
    (net (code "107") (name "unconnected-(U6-ETH_TXD1_(PG14)-Pad60)") (class "Default")
      (node (ref "U6") (pin "60") (pinfunction "ETH_TXD1_(PG14)_60") (pintype "unspecified+no_connect"))
    )
    (net (code "108") (name "unconnected-(U6-ETH_TX_EN_(PB11)-Pad16)") (class "Default")
      (node (ref "U6") (pin "16") (pinfunction "ETH_TX_EN_(PB11)_16") (pintype "unspecified+no_connect"))
    )
    (net (code "109") (name "unconnected-(U6-I2C3_CLK_(PH7)-Pad21)") (class "Default")
      (node (ref "U6") (pin "21") (pinfunction "I2C3_CLK_(PH7)_21") (pintype "unspecified+no_connect"))
    )
    (net (code "110") (name "unconnected-(U6-I2C3_DAT_(PH8)-Pad25)") (class "Default")
      (node (ref "U6") (pin "25") (pinfunction "I2C3_DAT_(PH8)_25") (pintype "unspecified+no_connect"))
    )
    (net (code "111") (name "unconnected-(U6-OTG_FS_OC_(PC2)-Pad82)") (class "Default")
      (node (ref "U6") (pin "82") (pinfunction "OTG_FS_OC_(PC2)_82") (pintype "unspecified+no_connect"))
    )
    (net (code "112") (name "unconnected-(U6-OTG_PWRON_(PH12)-Pad27)") (class "Default")
      (node (ref "U6") (pin "27") (pinfunction "OTG_PWRON_(PH12)_27") (pintype "unspecified+no_connect"))
    )
    (net (code "113") (name "unconnected-(U6-SD2_CLK_(PD6)-Pad47)") (class "Default")
      (node (ref "U6") (pin "47") (pinfunction "SD2_CLK_(PD6)_47") (pintype "unspecified+no_connect"))
    )
    (net (code "114") (name "unconnected-(U6-SD2_CMD_(PD7)-Pad48)") (class "Default")
      (node (ref "U6") (pin "48") (pinfunction "SD2_CMD_(PD7)_48") (pintype "unspecified+no_connect"))
    )
    (net (code "115") (name "unconnected-(U6-SD2_D0_(PG9)-Pad52)") (class "Default")
      (node (ref "U6") (pin "52") (pinfunction "SD2_D0_(PG9)_52") (pintype "unspecified+no_connect"))
    )
    (net (code "116") (name "unconnected-(U6-SD2_D1_(PG10)-Pad51)") (class "Default")
      (node (ref "U6") (pin "51") (pinfunction "SD2_D1_(PG10)_51") (pintype "unspecified+no_connect"))
    )
    (net (code "117") (name "unconnected-(U6-SD2_D2_(PG11)-Pad54)") (class "Default")
      (node (ref "U6") (pin "54") (pinfunction "SD2_D2_(PG11)_54") (pintype "unspecified+no_connect"))
    )
    (net (code "118") (name "unconnected-(U6-SD2_IN_L_(PG6)-Pad28)") (class "Default")
      (node (ref "U6") (pin "28") (pinfunction "SD2_IN_L_(PG6)_28") (pintype "unspecified+no_connect"))
    )
    (net (code "119") (name "unconnected-(U6-SPI3_CIPO_(PC11)-Pad38)") (class "Default")
      (node (ref "U6") (pin "38") (pinfunction "SPI3_CIPO_(PC11)_38") (pintype "unspecified+no_connect"))
    )
    (net (code "120") (name "unconnected-(U6-SPI3_CLK_(PC10)-Pad37)") (class "Default")
      (node (ref "U6") (pin "37") (pinfunction "SPI3_CLK_(PC10)_37") (pintype "unspecified+no_connect"))
    )
    (net (code "121") (name "unconnected-(U6-SPI3_COPI_(PB5)-Pad61)") (class "Default")
      (node (ref "U6") (pin "61") (pinfunction "SPI3_COPI_(PB5)_61") (pintype "unspecified+no_connect"))
    )
    (net (code "122") (name "unconnected-(U6-SPI5_CIPO_(PF8)-Pad71)") (class "Default")
      (node (ref "U6") (pin "71") (pinfunction "SPI5_CIPO_(PF8)_71") (pintype "unspecified+no_connect"))
    )
    (net (code "123") (name "unconnected-(U6-SPI5_CLK_(PH6)-Pad24)") (class "Default")
      (node (ref "U6") (pin "24") (pinfunction "SPI5_CLK_(PH6)_24") (pintype "unspecified+no_connect"))
    )
    (net (code "124") (name "unconnected-(U6-SPI5_COPI_(PF9)-Pad70)") (class "Default")
      (node (ref "U6") (pin "70") (pinfunction "SPI5_COPI_(PF9)_70") (pintype "unspecified+no_connect"))
    )
    (net (code "125") (name "unconnected-(U6-VBAT-Pad64)") (class "Default")
      (node (ref "U6") (pin "64") (pinfunction "VBAT_64") (pintype "input+no_connect"))
    )
    (net (code "126") (name "unconnected-(U7-3V3_EN-Pad16)") (class "Default")
      (node (ref "U7") (pin "16") (pinfunction "3V3_EN_16") (pintype "unspecified+no_connect"))
    )
    (net (code "127") (name "unconnected-(U12-INT-Pad8)") (class "Default")
      (node (ref "U12") (pin "8") (pinfunction "INT_8") (pintype "unspecified+no_connect"))
    )
    (net (code "128") (name "unconnected-(U12-NC-Pad7)") (class "Default")
      (node (ref "U12") (pin "7") (pinfunction "NC_7") (pintype "unspecified+no_connect"))
    )
    (net (code "129") (name "unconnected-(U12-N{slash}C-Pad10)") (class "Default")
      (node (ref "U12") (pin "10") (pinfunction "N/C_10") (pintype "unspecified+no_connect"))
    )
    (net (code "130") (name "unconnected-(U12-N{slash}C-Pad11)") (class "Default")
      (node (ref "U12") (pin "11") (pinfunction "N/C_11") (pintype "unspecified+no_connect"))
    )
  )
)
